# AS5047P.net
KiCad netlist of a schematic drawn in EAGLE
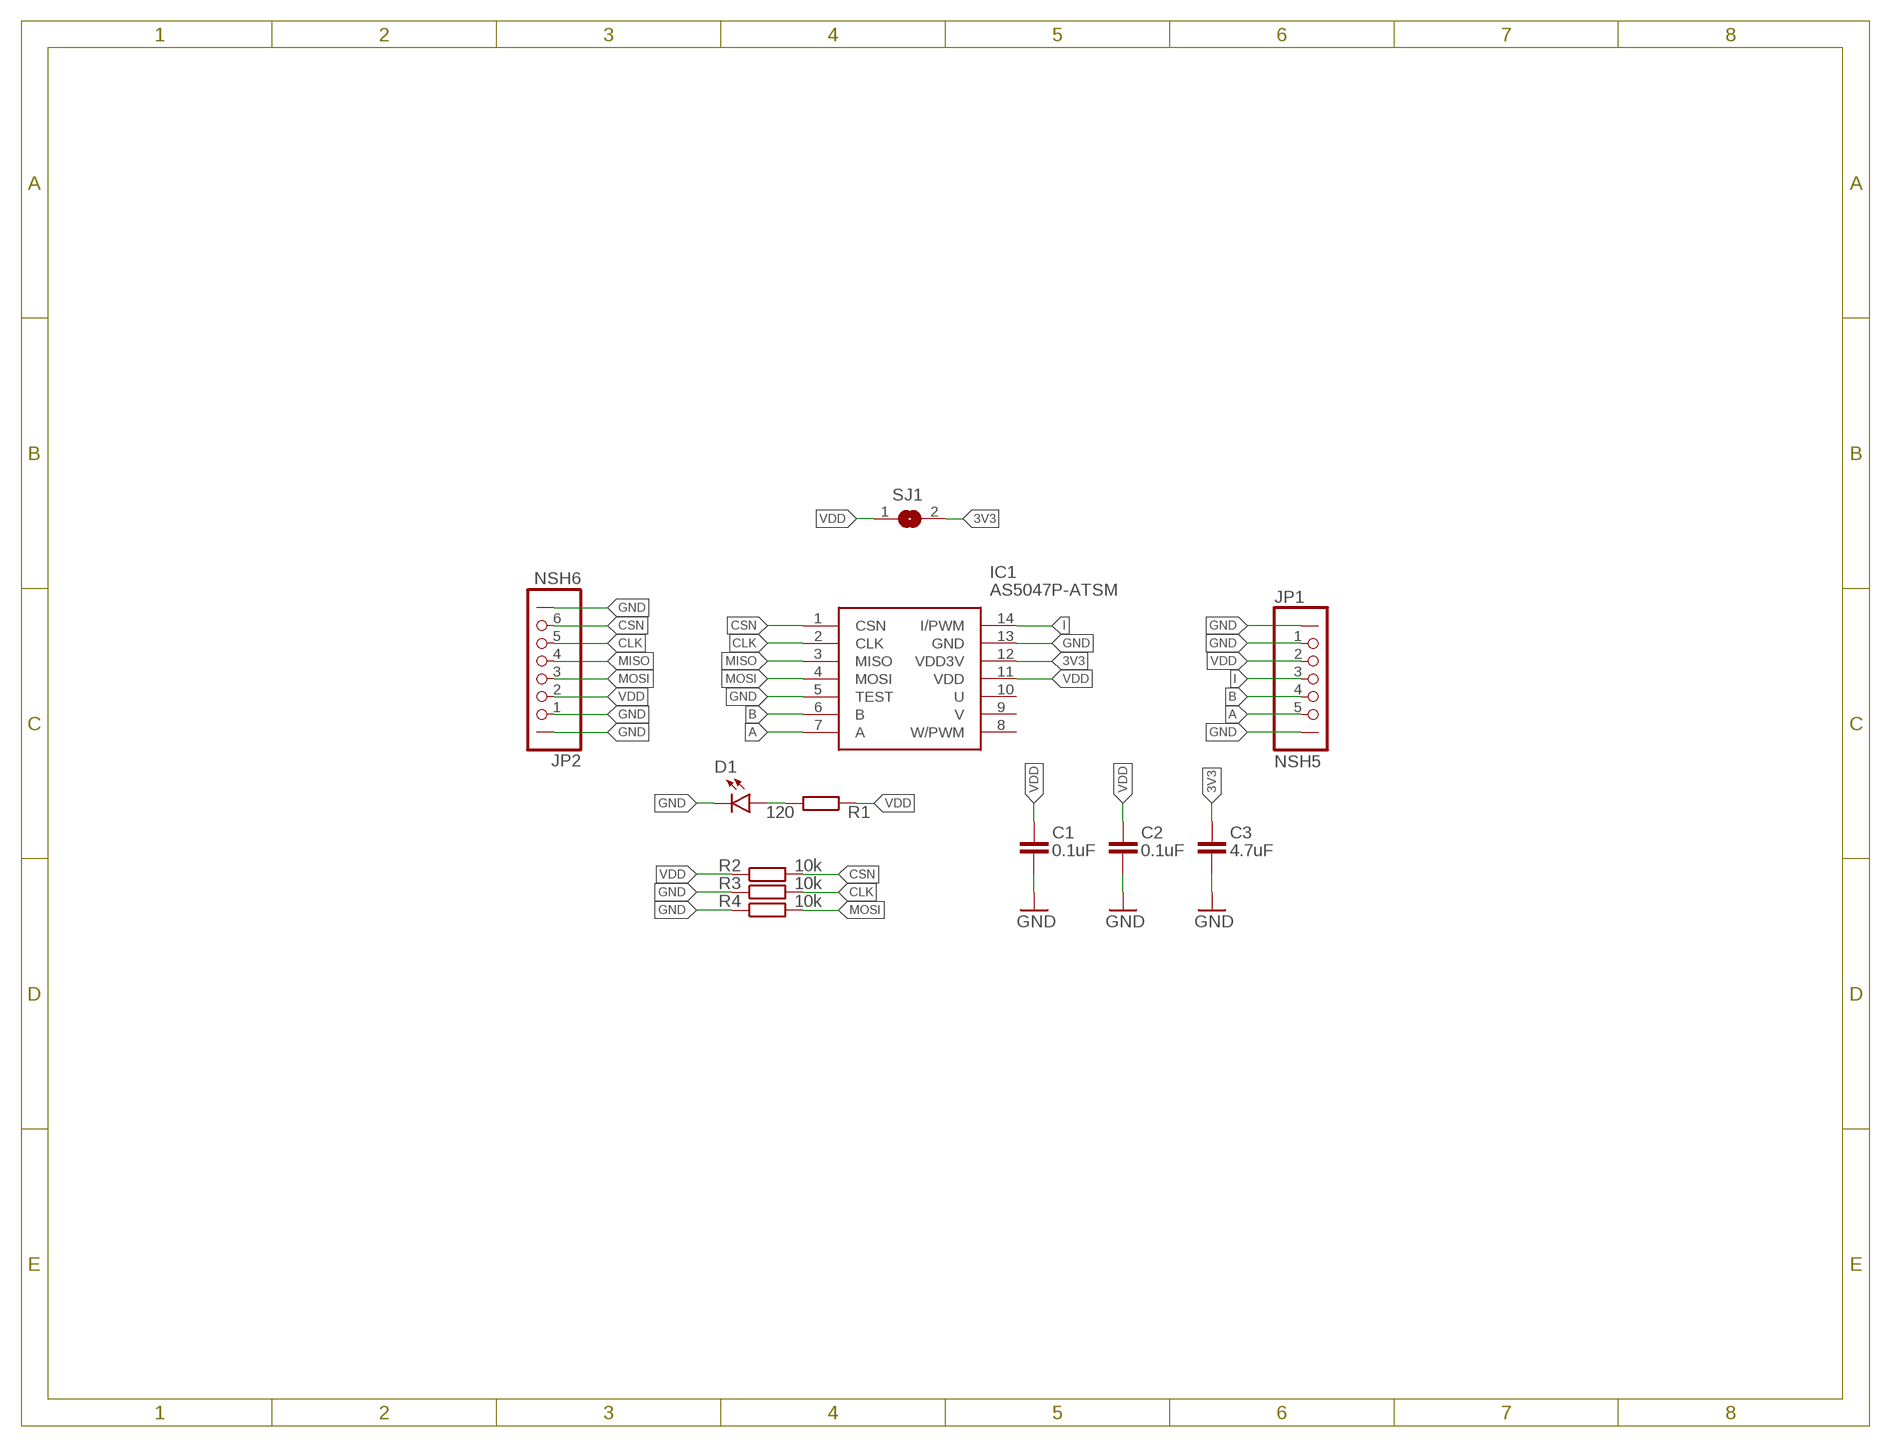
[diagram p0: schematic, sheet 1]

(export (version "E")
  (design (tool "Eeschema 10.0.6"))
  (components
    (comp (ref "C1")
      (value "0.1uF")
      (footprint "eagle-import:0402")
      (libsource (lib "eagle-import") (part "CCHIP-0402(1005-METRIC)_"))
    )
    (comp (ref "C2")
      (value "0.1uF")
      (footprint "eagle-import:0402")
      (libsource (lib "eagle-import") (part "CCHIP-0402(1005-METRIC)_"))
    )
    (comp (ref "C3")
      (value "4.7uF")
      (footprint "eagle-import:0402")
      (libsource (lib "eagle-import") (part "CCHIP-0402(1005-METRIC)_"))
    )
    (comp (ref "D1")
      (value "Yellow")
      (footprint "eagle-import:LEDC1005X25N_FLAT-B")
      (libsource (lib "eagle-import") (part "CHIP-FLAT-B_0402"))
    )
    (comp (ref "IC1")
      (value "AS5047P-ATSM")
      (footprint "eagle-import:SOP65P640X120-14L")
      (fields (field (name "MOUSER_PART_NUMBER") "985-AS5047P-ATSM"))
      (libsource (lib "eagle-import") (part "AS5047P-ATSM"))
    )
    (comp (ref "JP1")
      (value "NSH5")
      (footprint "eagle-import:NSH_5")
      (libsource (lib "eagle-import") (part "NSH5"))
    )
    (comp (ref "JP2")
      (value "NSH6")
      (footprint "eagle-import:NSH_6")
      (libsource (lib "eagle-import") (part "NSH6"))
    )
    (comp (ref "R1")
      (value "120")
      (footprint "eagle-import:0402")
      (libsource (lib "eagle-import") (part "RCHIP-0402(1005-METRIC)_"))
    )
    (comp (ref "R2")
      (value "10k")
      (footprint "eagle-import:0402")
      (libsource (lib "eagle-import") (part "RCHIP-0402(1005-METRIC)_"))
    )
    (comp (ref "R3")
      (value "10k")
      (footprint "eagle-import:0402")
      (libsource (lib "eagle-import") (part "RCHIP-0402(1005-METRIC)_"))
    )
    (comp (ref "R4")
      (value "10k")
      (footprint "eagle-import:0402")
      (libsource (lib "eagle-import") (part "RCHIP-0402(1005-METRIC)_"))
    )
    (comp (ref "SJ1") (value "SJ") (footprint "eagle-import:SJ") (libsource (lib "eagle-import") (part "SJ")))
  )
  (nets
    (net (code "1") (name "3V3") (class "Default")
      (node (ref "C3") (pin "1") (pinfunction "1_1") (pintype "passive"))
      (node (ref "IC1") (pin "12") (pinfunction "VDD3V_12") (pintype "bidirectional"))
      (node (ref "SJ1") (pin "2") (pinfunction "2_2") (pintype "passive"))
    )
    (net (code "2") (name "A") (class "Default")
      (node (ref "IC1") (pin "7") (pinfunction "A_7") (pintype "bidirectional"))
      (node (ref "JP1") (pin "5") (pinfunction "5_5") (pintype "passive"))
    )
    (net (code "3") (name "B") (class "Default")
      (node (ref "IC1") (pin "6") (pinfunction "B_6") (pintype "bidirectional"))
      (node (ref "JP1") (pin "4") (pinfunction "4_4") (pintype "passive"))
    )
    (net (code "4") (name "CLK") (class "Default")
      (node (ref "IC1") (pin "2") (pinfunction "CLK_2") (pintype "bidirectional"))
      (node (ref "JP2") (pin "5") (pinfunction "5_5") (pintype "passive"))
      (node (ref "R3") (pin "2") (pinfunction "2_2") (pintype "passive"))
    )
    (net (code "5") (name "CSN") (class "Default")
      (node (ref "IC1") (pin "1") (pinfunction "CSN_1") (pintype "bidirectional"))
      (node (ref "JP2") (pin "6") (pinfunction "6_6") (pintype "passive"))
      (node (ref "R2") (pin "2") (pinfunction "2_2") (pintype "passive"))
    )
    (net (code "6") (name "GND") (class "Default")
      (node (ref "C1") (pin "2") (pinfunction "2_2") (pintype "passive"))
      (node (ref "C2") (pin "2") (pinfunction "2_2") (pintype "passive"))
      (node (ref "C3") (pin "2") (pinfunction "2_2") (pintype "passive"))
      (node (ref "D1") (pin "C") (pinfunction "C_C") (pintype "passive"))
      (node (ref "IC1") (pin "13") (pinfunction "GND_13") (pintype "bidirectional"))
      (node (ref "IC1") (pin "5") (pinfunction "TEST_5") (pintype "bidirectional"))
      (node (ref "JP1") (pin "1") (pinfunction "1_1") (pintype "passive"))
      (node (ref "JP1") (pin "P-MOUNT1") (pinfunction "P$1_P-MOUNT1") (pintype "power_in"))
      (node (ref "JP1") (pin "P-MOUNT2") (pinfunction "P$2_P-MOUNT2") (pintype "power_in"))
      (node (ref "JP2") (pin "1") (pinfunction "1_1") (pintype "passive"))
      (node (ref "JP2") (pin "P-MOUNT1") (pinfunction "P$1_P-MOUNT1") (pintype "power_in"))
      (node (ref "JP2") (pin "P-MOUNT2") (pinfunction "P$2_P-MOUNT2") (pintype "power_in"))
      (node (ref "R3") (pin "1") (pinfunction "1_1") (pintype "passive"))
      (node (ref "R4") (pin "1") (pinfunction "1_1") (pintype "passive"))
    )
    (net (code "7") (name "I") (class "Default")
      (node (ref "IC1") (pin "14") (pinfunction "I/PWM_14") (pintype "bidirectional"))
      (node (ref "JP1") (pin "3") (pinfunction "3_3") (pintype "passive"))
    )
    (net (code "8") (name "MISO") (class "Default")
      (node (ref "IC1") (pin "3") (pinfunction "MISO_3") (pintype "bidirectional"))
      (node (ref "JP2") (pin "4") (pinfunction "4_4") (pintype "passive"))
    )
    (net (code "9") (name "MOSI") (class "Default")
      (node (ref "IC1") (pin "4") (pinfunction "MOSI_4") (pintype "bidirectional"))
      (node (ref "JP2") (pin "3") (pinfunction "3_3") (pintype "passive"))
      (node (ref "R4") (pin "2") (pinfunction "2_2") (pintype "passive"))
    )
    (net (code "10") (name "Net-(D1-PadA)") (class "Default")
      (node (ref "D1") (pin "A") (pinfunction "A_A") (pintype "passive"))
      (node (ref "R1") (pin "2") (pinfunction "2_2") (pintype "passive"))
    )
    (net (code "11") (name "VDD") (class "Default")
      (node (ref "C1") (pin "1") (pinfunction "1_1") (pintype "passive"))
      (node (ref "C2") (pin "1") (pinfunction "1_1") (pintype "passive"))
      (node (ref "IC1") (pin "11") (pinfunction "VDD_11") (pintype "bidirectional"))
      (node (ref "JP1") (pin "2") (pinfunction "2_2") (pintype "passive"))
      (node (ref "JP2") (pin "2") (pinfunction "2_2") (pintype "passive"))
      (node (ref "R1") (pin "1") (pinfunction "1_1") (pintype "passive"))
      (node (ref "R2") (pin "1") (pinfunction "1_1") (pintype "passive"))
      (node (ref "SJ1") (pin "1") (pinfunction "1_1") (pintype "passive"))
    )
    (net (code "12") (name "unconnected-(IC1-U-Pad10)") (class "Default")
      (node (ref "IC1") (pin "10") (pinfunction "U_10") (pintype "bidirectional"))
    )
    (net (code "13") (name "unconnected-(IC1-V-Pad9)") (class "Default")
      (node (ref "IC1") (pin "9") (pinfunction "V_9") (pintype "bidirectional"))
    )
    (net (code "14") (name "unconnected-(IC1-W{slash}PWM-Pad8)") (class "Default")
      (node (ref "IC1") (pin "8") (pinfunction "W/PWM_8") (pintype "bidirectional"))
    )
  )
)
